# Rooftop_Unit_for_AgOpenGPS.net
KiCad netlist of a schematic drawn in Altium Designer
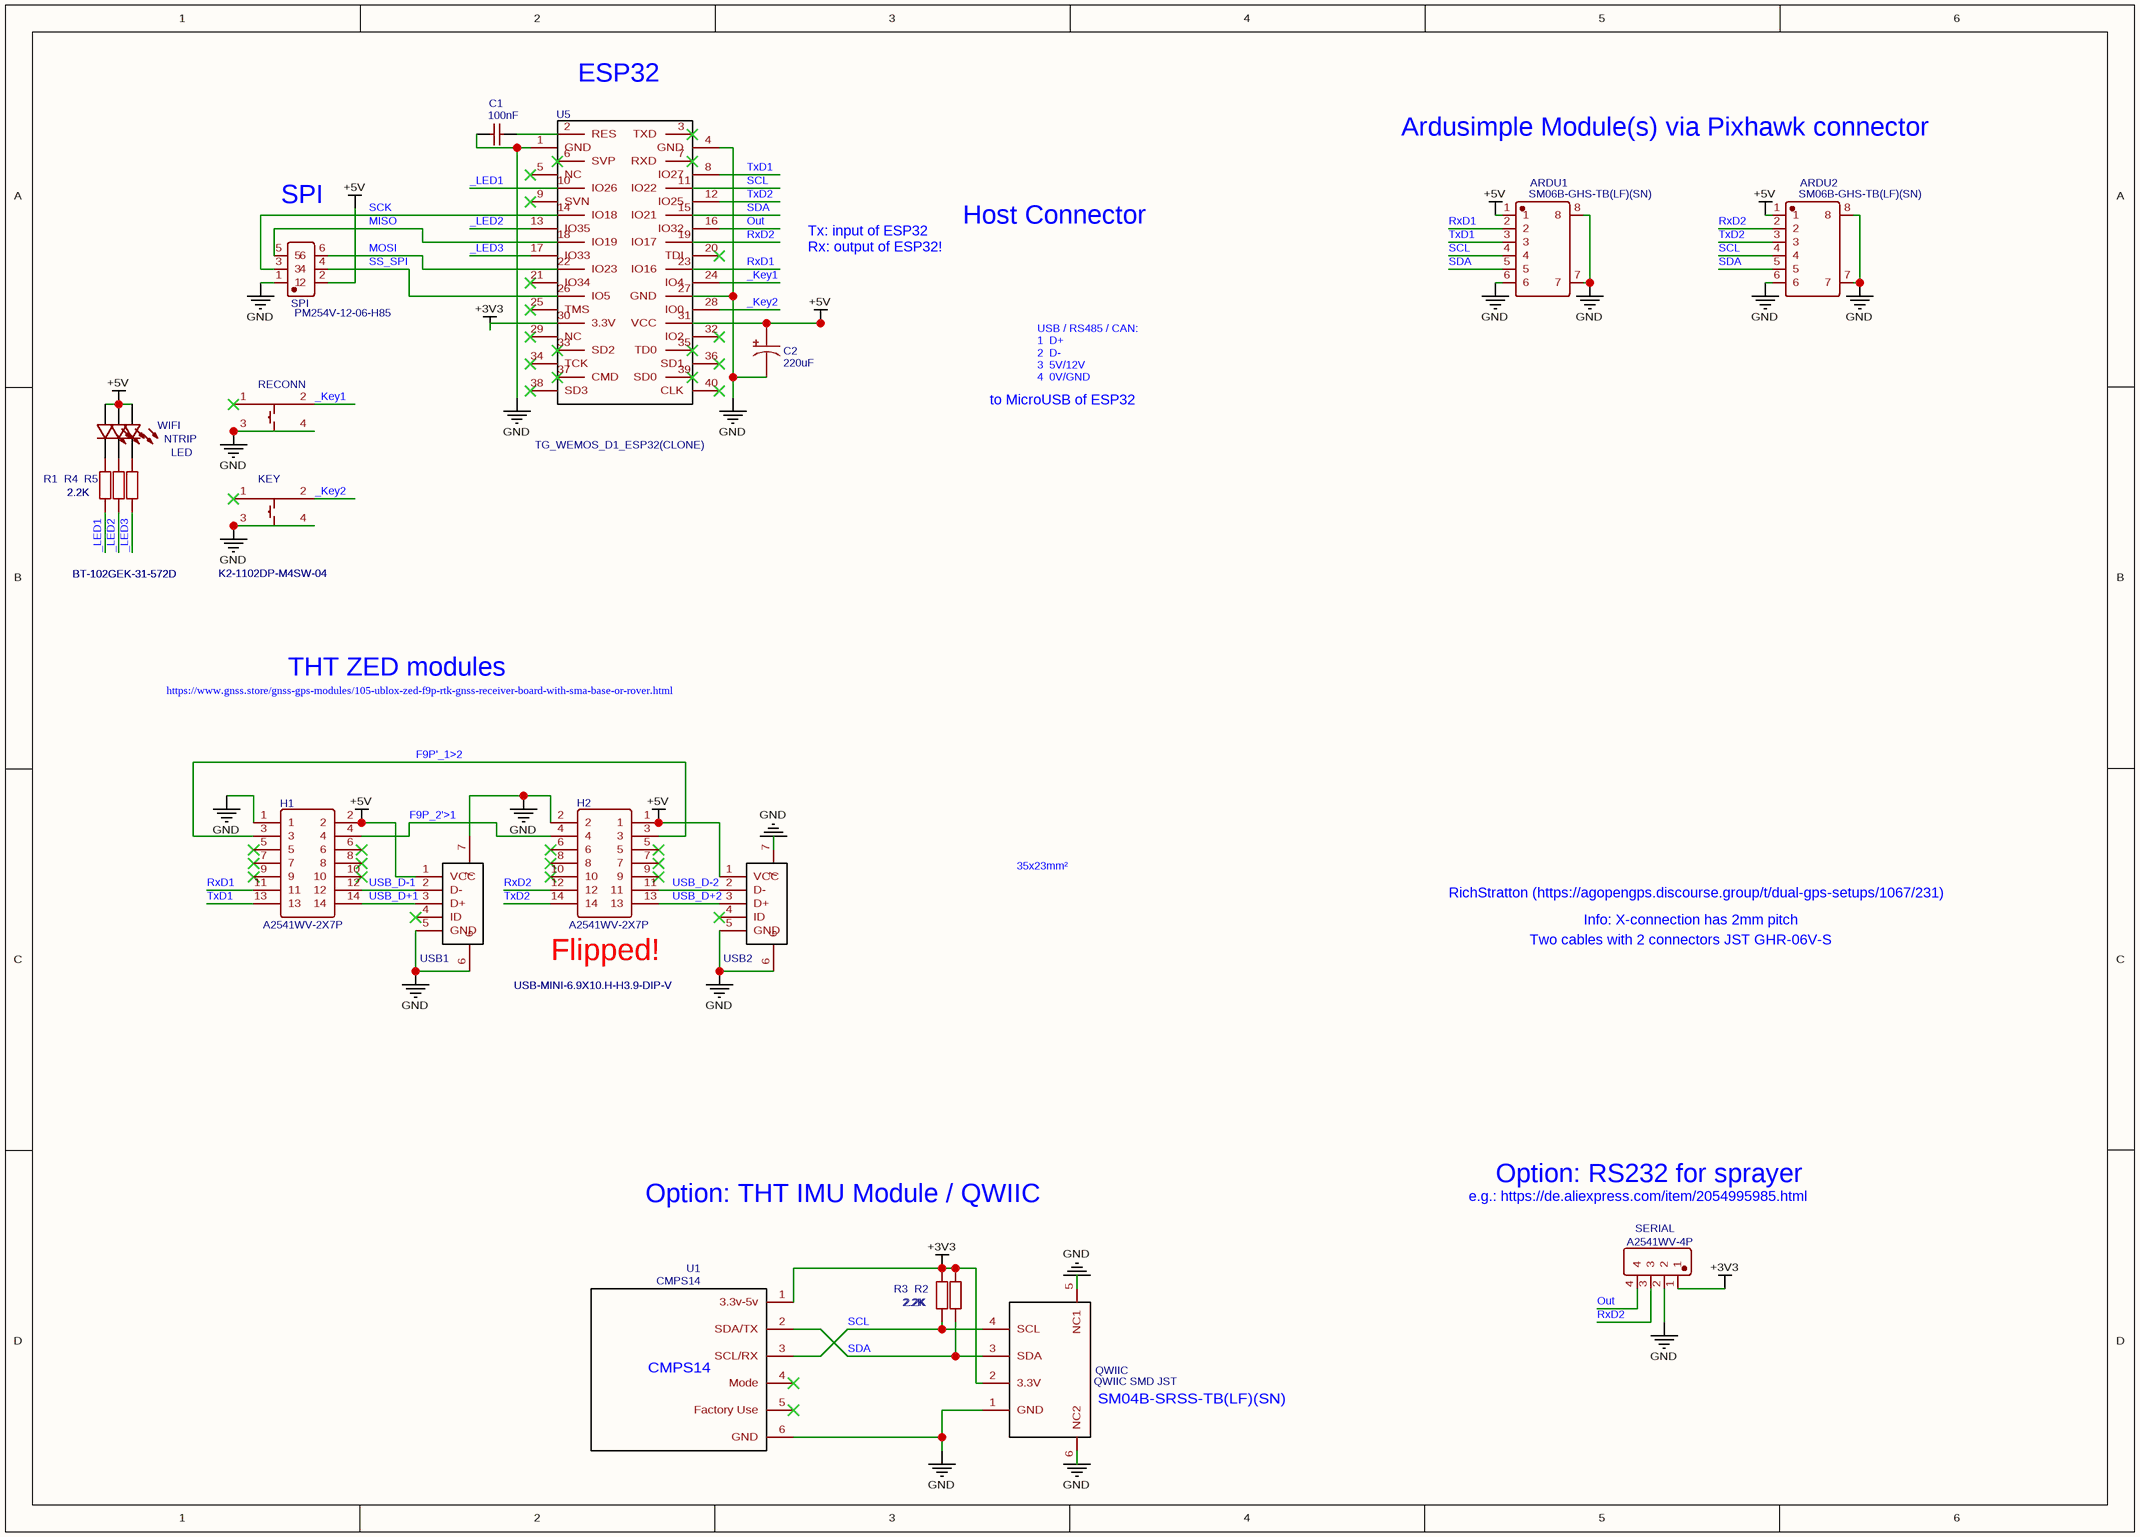
[diagram p0: Rooftop Unit for AgOpenGPS.schdoc]

(export (version "E")
  (design (tool "Eeschema 10.0.6"))
  (components
    (comp (ref "ARDU1")
      (value "SM06B-GHS-TB(LF)(SN)")
      (fields (field (name "BOM_SUPPLIER PART") "C133065") (field (name "CONTRIBUTOR") "LCSC"))
      (libsource (lib "altium-import") (part "root_0_SM06B-GHS-TB(LF)(SN)_"))
    )
    (comp (ref "ARDU2")
      (value "SM06B-GHS-TB(LF)(SN)")
      (fields (field (name "BOM_SUPPLIER PART") "C133065") (field (name "CONTRIBUTOR") "LCSC"))
      (libsource (lib "altium-import") (part "root_0_SM06B-GHS-TB(LF)(SN)_"))
    )
    (comp (ref "C1")
      (value "100nF")
      (fields
        (field (name "BOM_SUPPLIER PART") "C236029")
        (field (name "BOM_MANUFACTURER PART") "C320C104K5R5TA7303")
        (field (name "CONTRIBUTOR") "LCSC")
      )
      (libsource (lib "altium-import") (part "root_0_100nF_"))
    )
    (comp (ref "C2")
      (value "220uF")
      (fields
        (field (name "BOM_SUPPLIER PART") "C225866")
        (field (name "BOM_MANUFACTURER PART") "UPW1A221MED1TD")
        (field (name "CONTRIBUTOR") "LCSC")
      )
      (libsource (lib "altium-import") (part "root_0_220uF_"))
    )
    (comp (ref "H1")
      (value "A2541WV-2X7P")
      (fields
        (field (name "BOM_SUPPLIER PART") "C225522")
        (field (name "BOM_MANUFACTURER PART") "A2541WV-2x7P")
        (field (name "CONTRIBUTOR") "LCSC")
      )
      (libsource (lib "") (part "root_0_A2541WV-2X7P__1"))
    )
    (comp (ref "H2")
      (value "A2541WV-2X7P")
      (fields
        (field (name "BOM_SUPPLIER PART") "C225522")
        (field (name "BOM_MANUFACTURER PART") "A2541WV-2x7P")
        (field (name "CONTRIBUTOR") "LCSC")
      )
      (libsource (lib "altium-import") (part "root_0_A2541WV-2X7P_"))
    )
    (comp (ref "KEY")
      (value "K2-1102DP-M4SW-04")
      (fields (field (name "BOM_SUPPLIER PART") "C136678") (field (name "CONTRIBUTOR") "LCSC"))
      (libsource (lib "altium-import") (part "root_0_K2-1102DP-M4SW-04_"))
    )
    (comp (ref "LED")
      (value "BT-102GEK-31-572D")
      (fields (field (name "BOM_SUPPLIER PART") "C93096"))
      (libsource (lib "altium-import") (part "root_3_BT-102GEK-31-572D_"))
    )
    (comp (ref "NTRIP")
      (value "BT-102GEK-31-572D")
      (fields (field (name "BOM_SUPPLIER PART") "C93096"))
      (libsource (lib "altium-import") (part "root_3_BT-102GEK-31-572D_"))
    )
    (comp (ref "QWIIC")
      (value "QWIIC SMD JST")
      (fields
        (field (name "BOM_MANUFACTURER PART") "SM04B-SRSS-TB(LF)(SN)")
        (field (name "BOM_SUPPLIER PART") "PRT-14417")
        (field (name "CONTRIBUTOR") "donhagen")
      )
      (libsource (lib "altium-import") (part "root_1_QWIIC SMD JST_"))
    )
    (comp (ref "R1")
      (value "2.2K")
      (fields
        (field (name "BOM_SUPPLIER PART") "C274429")
        (field (name "BOM_MANUFACTURER PART") "RNU18F2201A520NH")
        (field (name "CONTRIBUTOR") "LCSC")
      )
      (libsource (lib "altium-import") (part "root_1_2.2K_"))
    )
    (comp (ref "R2")
      (value "2.2K")
      (fields
        (field (name "BOM_SUPPLIER PART") "C274429")
        (field (name "BOM_MANUFACTURER PART") "RNU18F2201A520NH")
        (field (name "CONTRIBUTOR") "LCSC")
      )
      (libsource (lib "altium-import") (part "root_1_2.2K_"))
    )
    (comp (ref "R3")
      (value "2.2K")
      (fields
        (field (name "BOM_SUPPLIER PART") "C274429")
        (field (name "BOM_MANUFACTURER PART") "RNU18F2201A520NH")
        (field (name "CONTRIBUTOR") "LCSC")
      )
      (libsource (lib "altium-import") (part "root_1_2.2K_"))
    )
    (comp (ref "R4")
      (value "2.2K")
      (fields
        (field (name "BOM_SUPPLIER PART") "C274429")
        (field (name "BOM_MANUFACTURER PART") "RNU18F2201A520NH")
        (field (name "CONTRIBUTOR") "LCSC")
      )
      (libsource (lib "altium-import") (part "root_1_2.2K_"))
    )
    (comp (ref "R5")
      (value "2.2K")
      (fields
        (field (name "BOM_SUPPLIER PART") "C274429")
        (field (name "BOM_MANUFACTURER PART") "RNU18F2201A520NH")
        (field (name "CONTRIBUTOR") "LCSC")
      )
      (libsource (lib "altium-import") (part "root_1_2.2K_"))
    )
    (comp (ref "RECONN")
      (value "K2-1102DP-M4SW-04")
      (fields (field (name "BOM_SUPPLIER PART") "C136678") (field (name "CONTRIBUTOR") "LCSC"))
      (libsource (lib "altium-import") (part "root_0_K2-1102DP-M4SW-04_"))
    )
    (comp (ref "SERIAL")
      (value "A2541WV-4P")
      (fields (field (name "BOM_SUPPLIER PART") "C225479") (field (name "CONTRIBUTOR") "LCSC"))
      (libsource (lib "altium-import") (part "root_0_A2541WV-4P_"))
    )
    (comp (ref "SPI")
      (value "PM254V-12-06-H85")
      (fields (field (name "BOM_SUPPLIER PART") "C541853") (field (name "CONTRIBUTOR") "LCSC"))
      (libsource (lib "altium-import") (part "root_0_PM254V-12-06-H85_"))
    )
    (comp (ref "U1")
      (value "CMPS14")
      (fields (field (name "CONTRIBUTOR") "FixyNeko"))
      (libsource (lib "altium-import") (part "root_0_CMPS14_"))
    )
    (comp (ref "U5")
      (value "TG_WEMOS_D1_ESP32(CLONE)")
      (fields
        (field (name "BOM_MANUFACTURER PART") "New SchematicLib")
        (field (name "BOM_SUPPLIER PART") "undefined")
        (field (name "CONTRIBUTOR") "John Archbold")
      )
      (libsource (lib "altium-import") (part "root_0_TG_WEMOS_D1_ESP32(CLONE)_"))
    )
    (comp (ref "USB1")
      (value "USB-MINI-6.9X10.H-H3.9-DIP-V")
      (fields (field (name "BOM_SUPPLIER PART") "C13453") (field (name "CONTRIBUTOR") "LCSC"))
      (libsource (lib "altium-import") (part "root_3_USB-MINI-6.9X10.H-H3.9-DIP-V_"))
    )
    (comp (ref "USB2")
      (value "USB-MINI-6.9X10.H-H3.9-DIP-V")
      (fields (field (name "BOM_SUPPLIER PART") "C13453") (field (name "CONTRIBUTOR") "LCSC"))
      (libsource (lib "altium-import") (part "root_3_USB-MINI-6.9X10.H-H3.9-DIP-V_"))
    )
    (comp (ref "WIFI")
      (value "BT-102GEK-31-572D")
      (fields (field (name "BOM_SUPPLIER PART") "C93096"))
      (libsource (lib "altium-import") (part "root_3_BT-102GEK-31-572D_"))
    )
  )
  (nets
    (net (code "1") (name "+3V3") (class "Default")
      (node (ref "QWIIC") (pin "2") (pinfunction "3.3V_2") (pintype "passive"))
      (node (ref "R2") (pin "2") (pinfunction "2_2") (pintype "passive"))
      (node (ref "R3") (pin "2") (pinfunction "2_2") (pintype "passive"))
      (node (ref "SERIAL") (pin "1") (pinfunction "1_1") (pintype "passive"))
      (node (ref "U1") (pin "1") (pinfunction "3.3v-5v_1") (pintype "passive"))
      (node (ref "U5") (pin "30") (pinfunction "3.3V_30") (pintype "passive"))
    )
    (net (code "2") (name "+5V") (class "Default")
      (node (ref "ARDU1") (pin "1") (pinfunction "1_1") (pintype "passive"))
      (node (ref "ARDU2") (pin "1") (pinfunction "1_1") (pintype "passive"))
      (node (ref "C2") (pin "1") (pinfunction "1_1") (pintype "passive"))
      (node (ref "H1") (pin "2") (pinfunction "2_2") (pintype "passive"))
      (node (ref "H2") (pin "1") (pinfunction "1_1") (pintype "passive"))
      (node (ref "LED") (pin "1") (pinfunction "1_1") (pintype "passive"))
      (node (ref "NTRIP") (pin "1") (pinfunction "1_1") (pintype "passive"))
      (node (ref "SPI") (pin "2") (pinfunction "2_2") (pintype "passive"))
      (node (ref "U5") (pin "31") (pinfunction "VCC_31") (pintype "passive"))
      (node (ref "USB1") (pin "1") (pinfunction "VCC_1") (pintype "passive"))
      (node (ref "USB2") (pin "1") (pinfunction "VCC_1") (pintype "passive"))
      (node (ref "WIFI") (pin "1") (pinfunction "1_1") (pintype "passive"))
    )
    (net (code "3") (name "/F9P'_1>2") (class "Default")
      (node (ref "H1") (pin "3") (pinfunction "3_3") (pintype "passive"))
      (node (ref "H2") (pin "3") (pinfunction "3_3") (pintype "passive"))
    )
    (net (code "4") (name "/F9P_2'>1") (class "Default")
      (node (ref "H1") (pin "4") (pinfunction "4_4") (pintype "passive"))
      (node (ref "H2") (pin "4") (pinfunction "4_4") (pintype "passive"))
    )
    (net (code "5") (name "/MISO") (class "Default")
      (node (ref "SPI") (pin "5") (pinfunction "5_5") (pintype "passive"))
      (node (ref "U5") (pin "18") (pinfunction "IO19_18") (pintype "passive"))
    )
    (net (code "6") (name "/MOSI") (class "Default")
      (node (ref "SPI") (pin "6") (pinfunction "6_6") (pintype "passive"))
      (node (ref "U5") (pin "22") (pinfunction "IO23_22") (pintype "passive"))
    )
    (net (code "7") (name "/Out") (class "Default")
      (node (ref "SERIAL") (pin "4") (pinfunction "4_4") (pintype "passive"))
      (node (ref "U5") (pin "16") (pinfunction "IO32_16") (pintype "passive"))
    )
    (net (code "8") (name "/RxD1") (class "Default")
      (node (ref "ARDU1") (pin "2") (pinfunction "2_2") (pintype "passive"))
      (node (ref "H1") (pin "11") (pinfunction "11_11") (pintype "passive"))
      (node (ref "U5") (pin "23") (pinfunction "IO16_23") (pintype "passive"))
    )
    (net (code "9") (name "/RxD2") (class "Default")
      (node (ref "ARDU2") (pin "2") (pinfunction "2_2") (pintype "passive"))
      (node (ref "H2") (pin "12") (pinfunction "12_12") (pintype "passive"))
      (node (ref "SERIAL") (pin "3") (pinfunction "3_3") (pintype "passive"))
      (node (ref "U5") (pin "19") (pinfunction "IO17_19") (pintype "passive"))
    )
    (net (code "10") (name "/SCK") (class "Default")
      (node (ref "SPI") (pin "3") (pinfunction "3_3") (pintype "passive"))
      (node (ref "U5") (pin "14") (pinfunction "IO18_14") (pintype "passive"))
    )
    (net (code "11") (name "/SCL") (class "Default")
      (node (ref "ARDU1") (pin "4") (pinfunction "4_4") (pintype "passive"))
      (node (ref "ARDU2") (pin "4") (pinfunction "4_4") (pintype "passive"))
      (node (ref "QWIIC") (pin "4") (pinfunction "SCL_4") (pintype "passive"))
      (node (ref "R3") (pin "1") (pinfunction "1_1") (pintype "passive"))
      (node (ref "U1") (pin "3") (pinfunction "SCL/RX_3") (pintype "passive"))
      (node (ref "U5") (pin "11") (pinfunction "IO22_11") (pintype "passive"))
    )
    (net (code "12") (name "/SDA") (class "Default")
      (node (ref "ARDU1") (pin "5") (pinfunction "5_5") (pintype "passive"))
      (node (ref "ARDU2") (pin "5") (pinfunction "5_5") (pintype "passive"))
      (node (ref "QWIIC") (pin "3") (pinfunction "SDA_3") (pintype "passive"))
      (node (ref "R2") (pin "1") (pinfunction "1_1") (pintype "passive"))
      (node (ref "U1") (pin "2") (pinfunction "SDA/TX_2") (pintype "passive"))
      (node (ref "U5") (pin "15") (pinfunction "IO21_15") (pintype "passive"))
    )
    (net (code "13") (name "/SS_SPI") (class "Default")
      (node (ref "SPI") (pin "4") (pinfunction "4_4") (pintype "passive"))
      (node (ref "U5") (pin "26") (pinfunction "IO5_26") (pintype "passive"))
    )
    (net (code "14") (name "/TxD1") (class "Default")
      (node (ref "ARDU1") (pin "3") (pinfunction "3_3") (pintype "passive"))
      (node (ref "H1") (pin "13") (pinfunction "13_13") (pintype "passive"))
      (node (ref "U5") (pin "8") (pinfunction "IO27_8") (pintype "passive"))
    )
    (net (code "15") (name "/TxD2") (class "Default")
      (node (ref "ARDU2") (pin "3") (pinfunction "3_3") (pintype "passive"))
      (node (ref "H2") (pin "14") (pinfunction "14_14") (pintype "passive"))
      (node (ref "U5") (pin "12") (pinfunction "IO25_12") (pintype "passive"))
    )
    (net (code "16") (name "/USB_D+1") (class "Default")
      (node (ref "H1") (pin "14") (pinfunction "14_14") (pintype "passive"))
      (node (ref "USB1") (pin "3") (pinfunction "D+_3") (pintype "passive"))
    )
    (net (code "17") (name "/USB_D+2") (class "Default")
      (node (ref "H2") (pin "13") (pinfunction "13_13") (pintype "passive"))
      (node (ref "USB2") (pin "3") (pinfunction "D+_3") (pintype "passive"))
    )
    (net (code "18") (name "/USB_D-1") (class "Default")
      (node (ref "H1") (pin "12") (pinfunction "12_12") (pintype "passive"))
      (node (ref "USB1") (pin "2") (pinfunction "D-_2") (pintype "passive"))
    )
    (net (code "19") (name "/USB_D-2") (class "Default")
      (node (ref "H2") (pin "11") (pinfunction "11_11") (pintype "passive"))
      (node (ref "USB2") (pin "2") (pinfunction "D-_2") (pintype "passive"))
    )
    (net (code "20") (name "/_Key1") (class "Default")
      (node (ref "RECONN") (pin "2") (pinfunction "2_2") (pintype "passive"))
      (node (ref "U5") (pin "24") (pinfunction "IO4_24") (pintype "passive"))
    )
    (net (code "21") (name "/_Key2") (class "Default")
      (node (ref "KEY") (pin "2") (pinfunction "2_2") (pintype "passive"))
      (node (ref "U5") (pin "28") (pinfunction "IO0_28") (pintype "passive"))
    )
    (net (code "22") (name "/_LED1") (class "Default")
      (node (ref "R1") (pin "1") (pinfunction "1_1") (pintype "passive"))
      (node (ref "U5") (pin "10") (pinfunction "IO26_10") (pintype "passive"))
    )
    (net (code "23") (name "/_LED2") (class "Default")
      (node (ref "R4") (pin "1") (pinfunction "1_1") (pintype "passive"))
      (node (ref "U5") (pin "13") (pinfunction "IO35_13") (pintype "passive"))
    )
    (net (code "24") (name "/_LED3") (class "Default")
      (node (ref "R5") (pin "1") (pinfunction "1_1") (pintype "passive"))
      (node (ref "U5") (pin "17") (pinfunction "IO33_17") (pintype "passive"))
    )
    (net (code "25") (name "GND") (class "Default")
      (node (ref "ARDU1") (pin "6") (pinfunction "6_6") (pintype "passive"))
      (node (ref "ARDU1") (pin "7") (pinfunction "7_7") (pintype "passive"))
      (node (ref "ARDU1") (pin "8") (pinfunction "8_8") (pintype "passive"))
      (node (ref "ARDU2") (pin "6") (pinfunction "6_6") (pintype "passive"))
      (node (ref "ARDU2") (pin "7") (pinfunction "7_7") (pintype "passive"))
      (node (ref "ARDU2") (pin "8") (pinfunction "8_8") (pintype "passive"))
      (node (ref "C1") (pin "1") (pinfunction "1_1") (pintype "passive"))
      (node (ref "C2") (pin "2") (pinfunction "2_2") (pintype "passive"))
      (node (ref "H1") (pin "1") (pinfunction "1_1") (pintype "passive"))
      (node (ref "H2") (pin "2") (pinfunction "2_2") (pintype "passive"))
      (node (ref "KEY") (pin "3") (pinfunction "3_3") (pintype "passive"))
      (node (ref "KEY") (pin "4") (pinfunction "4_4") (pintype "passive"))
      (node (ref "QWIIC") (pin "1") (pinfunction "GND_1") (pintype "passive"))
      (node (ref "QWIIC") (pin "5") (pinfunction "NC1_5") (pintype "passive"))
      (node (ref "QWIIC") (pin "6") (pinfunction "NC2_6") (pintype "passive"))
      (node (ref "RECONN") (pin "3") (pinfunction "3_3") (pintype "passive"))
      (node (ref "RECONN") (pin "4") (pinfunction "4_4") (pintype "passive"))
      (node (ref "SERIAL") (pin "2") (pinfunction "2_2") (pintype "passive"))
      (node (ref "SPI") (pin "1") (pinfunction "1_1") (pintype "passive"))
      (node (ref "U1") (pin "6") (pinfunction "GND_6") (pintype "passive"))
      (node (ref "U5") (pin "1") (pinfunction "GND_1") (pintype "passive"))
      (node (ref "U5") (pin "27") (pinfunction "GND_27") (pintype "passive"))
      (node (ref "U5") (pin "4") (pinfunction "GND_4") (pintype "passive"))
      (node (ref "USB1") (pin "5") (pinfunction "GND_5") (pintype "passive"))
      (node (ref "USB1") (pin "6") (pinfunction "6_6") (pintype "passive"))
      (node (ref "USB1") (pin "7") (pinfunction "7_7") (pintype "passive"))
      (node (ref "USB2") (pin "5") (pinfunction "GND_5") (pintype "passive"))
      (node (ref "USB2") (pin "6") (pinfunction "6_6") (pintype "passive"))
      (node (ref "USB2") (pin "7") (pinfunction "7_7") (pintype "passive"))
    )
    (net (code "26") (name "Net-(LED-Pad2)") (class "Default")
      (node (ref "LED") (pin "2") (pinfunction "2_2") (pintype "passive"))
      (node (ref "R5") (pin "2") (pinfunction "2_2") (pintype "passive"))
    )
    (net (code "27") (name "Net-(NTRIP-Pad2)") (class "Default")
      (node (ref "NTRIP") (pin "2") (pinfunction "2_2") (pintype "passive"))
      (node (ref "R4") (pin "2") (pinfunction "2_2") (pintype "passive"))
    )
    (net (code "28") (name "Net-(R1-Pad2)") (class "Default")
      (node (ref "R1") (pin "2") (pinfunction "2_2") (pintype "passive"))
      (node (ref "WIFI") (pin "2") (pinfunction "2_2") (pintype "passive"))
    )
    (net (code "29") (name "Net-(U5-RES)") (class "Default")
      (node (ref "C1") (pin "2") (pinfunction "2_2") (pintype "passive"))
      (node (ref "U5") (pin "2") (pinfunction "RES_2") (pintype "passive"))
    )
    (net (code "30") (name "unconnected-(H1-Pad5)") (class "Default")
      (node (ref "H1") (pin "5") (pinfunction "5_5") (pintype "passive+no_connect"))
    )
    (net (code "31") (name "unconnected-(H1-Pad6)") (class "Default")
      (node (ref "H1") (pin "6") (pinfunction "6_6") (pintype "passive+no_connect"))
    )
    (net (code "32") (name "unconnected-(H1-Pad7)") (class "Default")
      (node (ref "H1") (pin "7") (pinfunction "7_7") (pintype "passive+no_connect"))
    )
    (net (code "33") (name "unconnected-(H1-Pad8)") (class "Default")
      (node (ref "H1") (pin "8") (pinfunction "8_8") (pintype "passive+no_connect"))
    )
    (net (code "34") (name "unconnected-(H1-Pad9)") (class "Default")
      (node (ref "H1") (pin "9") (pinfunction "9_9") (pintype "passive+no_connect"))
    )
    (net (code "35") (name "unconnected-(H1-Pad10)") (class "Default")
      (node (ref "H1") (pin "10") (pinfunction "10_10") (pintype "passive+no_connect"))
    )
    (net (code "36") (name "unconnected-(H2-Pad5)") (class "Default")
      (node (ref "H2") (pin "5") (pinfunction "5_5") (pintype "passive+no_connect"))
    )
    (net (code "37") (name "unconnected-(H2-Pad6)") (class "Default")
      (node (ref "H2") (pin "6") (pinfunction "6_6") (pintype "passive+no_connect"))
    )
    (net (code "38") (name "unconnected-(H2-Pad7)") (class "Default")
      (node (ref "H2") (pin "7") (pinfunction "7_7") (pintype "passive+no_connect"))
    )
    (net (code "39") (name "unconnected-(H2-Pad8)") (class "Default")
      (node (ref "H2") (pin "8") (pinfunction "8_8") (pintype "passive+no_connect"))
    )
    (net (code "40") (name "unconnected-(H2-Pad9)") (class "Default")
      (node (ref "H2") (pin "9") (pinfunction "9_9") (pintype "passive+no_connect"))
    )
    (net (code "41") (name "unconnected-(H2-Pad10)") (class "Default")
      (node (ref "H2") (pin "10") (pinfunction "10_10") (pintype "passive+no_connect"))
    )
    (net (code "42") (name "unconnected-(KEY-Pad1)") (class "Default")
      (node (ref "KEY") (pin "1") (pinfunction "1_1") (pintype "passive+no_connect"))
    )
    (net (code "43") (name "unconnected-(RECONN-Pad1)") (class "Default")
      (node (ref "RECONN") (pin "1") (pinfunction "1_1") (pintype "passive+no_connect"))
    )
    (net (code "44") (name "unconnected-(U1-Factory_Use-Pad5)") (class "Default")
      (node (ref "U1") (pin "5") (pinfunction "Factory_Use_5") (pintype "passive+no_connect"))
    )
    (net (code "45") (name "unconnected-(U1-Mode-Pad4)") (class "Default")
      (node (ref "U1") (pin "4") (pinfunction "Mode_4") (pintype "passive+no_connect"))
    )
    (net (code "46") (name "unconnected-(U5-CLK-Pad40)") (class "Default")
      (node (ref "U5") (pin "40") (pinfunction "CLK_40") (pintype "passive+no_connect"))
    )
    (net (code "47") (name "unconnected-(U5-CMD-Pad37)") (class "Default")
      (node (ref "U5") (pin "37") (pinfunction "CMD_37") (pintype "passive+no_connect"))
    )
    (net (code "48") (name "unconnected-(U5-IO2-Pad32)") (class "Default")
      (node (ref "U5") (pin "32") (pinfunction "IO2_32") (pintype "passive+no_connect"))
    )
    (net (code "49") (name "unconnected-(U5-IO34-Pad21)") (class "Default")
      (node (ref "U5") (pin "21") (pinfunction "IO34_21") (pintype "passive+no_connect"))
    )
    (net (code "50") (name "unconnected-(U5-NC-Pad5)") (class "Default")
      (node (ref "U5") (pin "5") (pinfunction "NC_5") (pintype "passive+no_connect"))
    )
    (net (code "51") (name "unconnected-(U5-NC-Pad29)") (class "Default")
      (node (ref "U5") (pin "29") (pinfunction "NC_29") (pintype "passive+no_connect"))
    )
    (net (code "52") (name "unconnected-(U5-RXD-Pad7)") (class "Default")
      (node (ref "U5") (pin "7") (pinfunction "RXD_7") (pintype "passive+no_connect"))
    )
    (net (code "53") (name "unconnected-(U5-SD0-Pad39)") (class "Default")
      (node (ref "U5") (pin "39") (pinfunction "SD0_39") (pintype "passive+no_connect"))
    )
    (net (code "54") (name "unconnected-(U5-SD1-Pad36)") (class "Default")
      (node (ref "U5") (pin "36") (pinfunction "SD1_36") (pintype "passive+no_connect"))
    )
    (net (code "55") (name "unconnected-(U5-SD2-Pad33)") (class "Default")
      (node (ref "U5") (pin "33") (pinfunction "SD2_33") (pintype "passive+no_connect"))
    )
    (net (code "56") (name "unconnected-(U5-SD3-Pad38)") (class "Default")
      (node (ref "U5") (pin "38") (pinfunction "SD3_38") (pintype "passive+no_connect"))
    )
    (net (code "57") (name "unconnected-(U5-SVN-Pad9)") (class "Default")
      (node (ref "U5") (pin "9") (pinfunction "SVN_9") (pintype "passive+no_connect"))
    )
    (net (code "58") (name "unconnected-(U5-SVP-Pad6)") (class "Default")
      (node (ref "U5") (pin "6") (pinfunction "SVP_6") (pintype "passive+no_connect"))
    )
    (net (code "59") (name "unconnected-(U5-TCK-Pad34)") (class "Default")
      (node (ref "U5") (pin "34") (pinfunction "TCK_34") (pintype "passive+no_connect"))
    )
    (net (code "60") (name "unconnected-(U5-TD0-Pad35)") (class "Default")
      (node (ref "U5") (pin "35") (pinfunction "TD0_35") (pintype "passive+no_connect"))
    )
    (net (code "61") (name "unconnected-(U5-TDI-Pad20)") (class "Default")
      (node (ref "U5") (pin "20") (pinfunction "TDI_20") (pintype "passive+no_connect"))
    )
    (net (code "62") (name "unconnected-(U5-TMS-Pad25)") (class "Default")
      (node (ref "U5") (pin "25") (pinfunction "TMS_25") (pintype "passive+no_connect"))
    )
    (net (code "63") (name "unconnected-(U5-TXD-Pad3)") (class "Default")
      (node (ref "U5") (pin "3") (pinfunction "TXD_3") (pintype "passive+no_connect"))
    )
    (net (code "64") (name "unconnected-(USB1-ID-Pad4)") (class "Default")
      (node (ref "USB1") (pin "4") (pinfunction "ID_4") (pintype "passive+no_connect"))
    )
    (net (code "65") (name "unconnected-(USB2-ID-Pad4)") (class "Default")
      (node (ref "USB2") (pin "4") (pinfunction "ID_4") (pintype "passive+no_connect"))
    )
  )
)
